# untitled.net
KiCad netlist of a schematic drawn in EAGLE
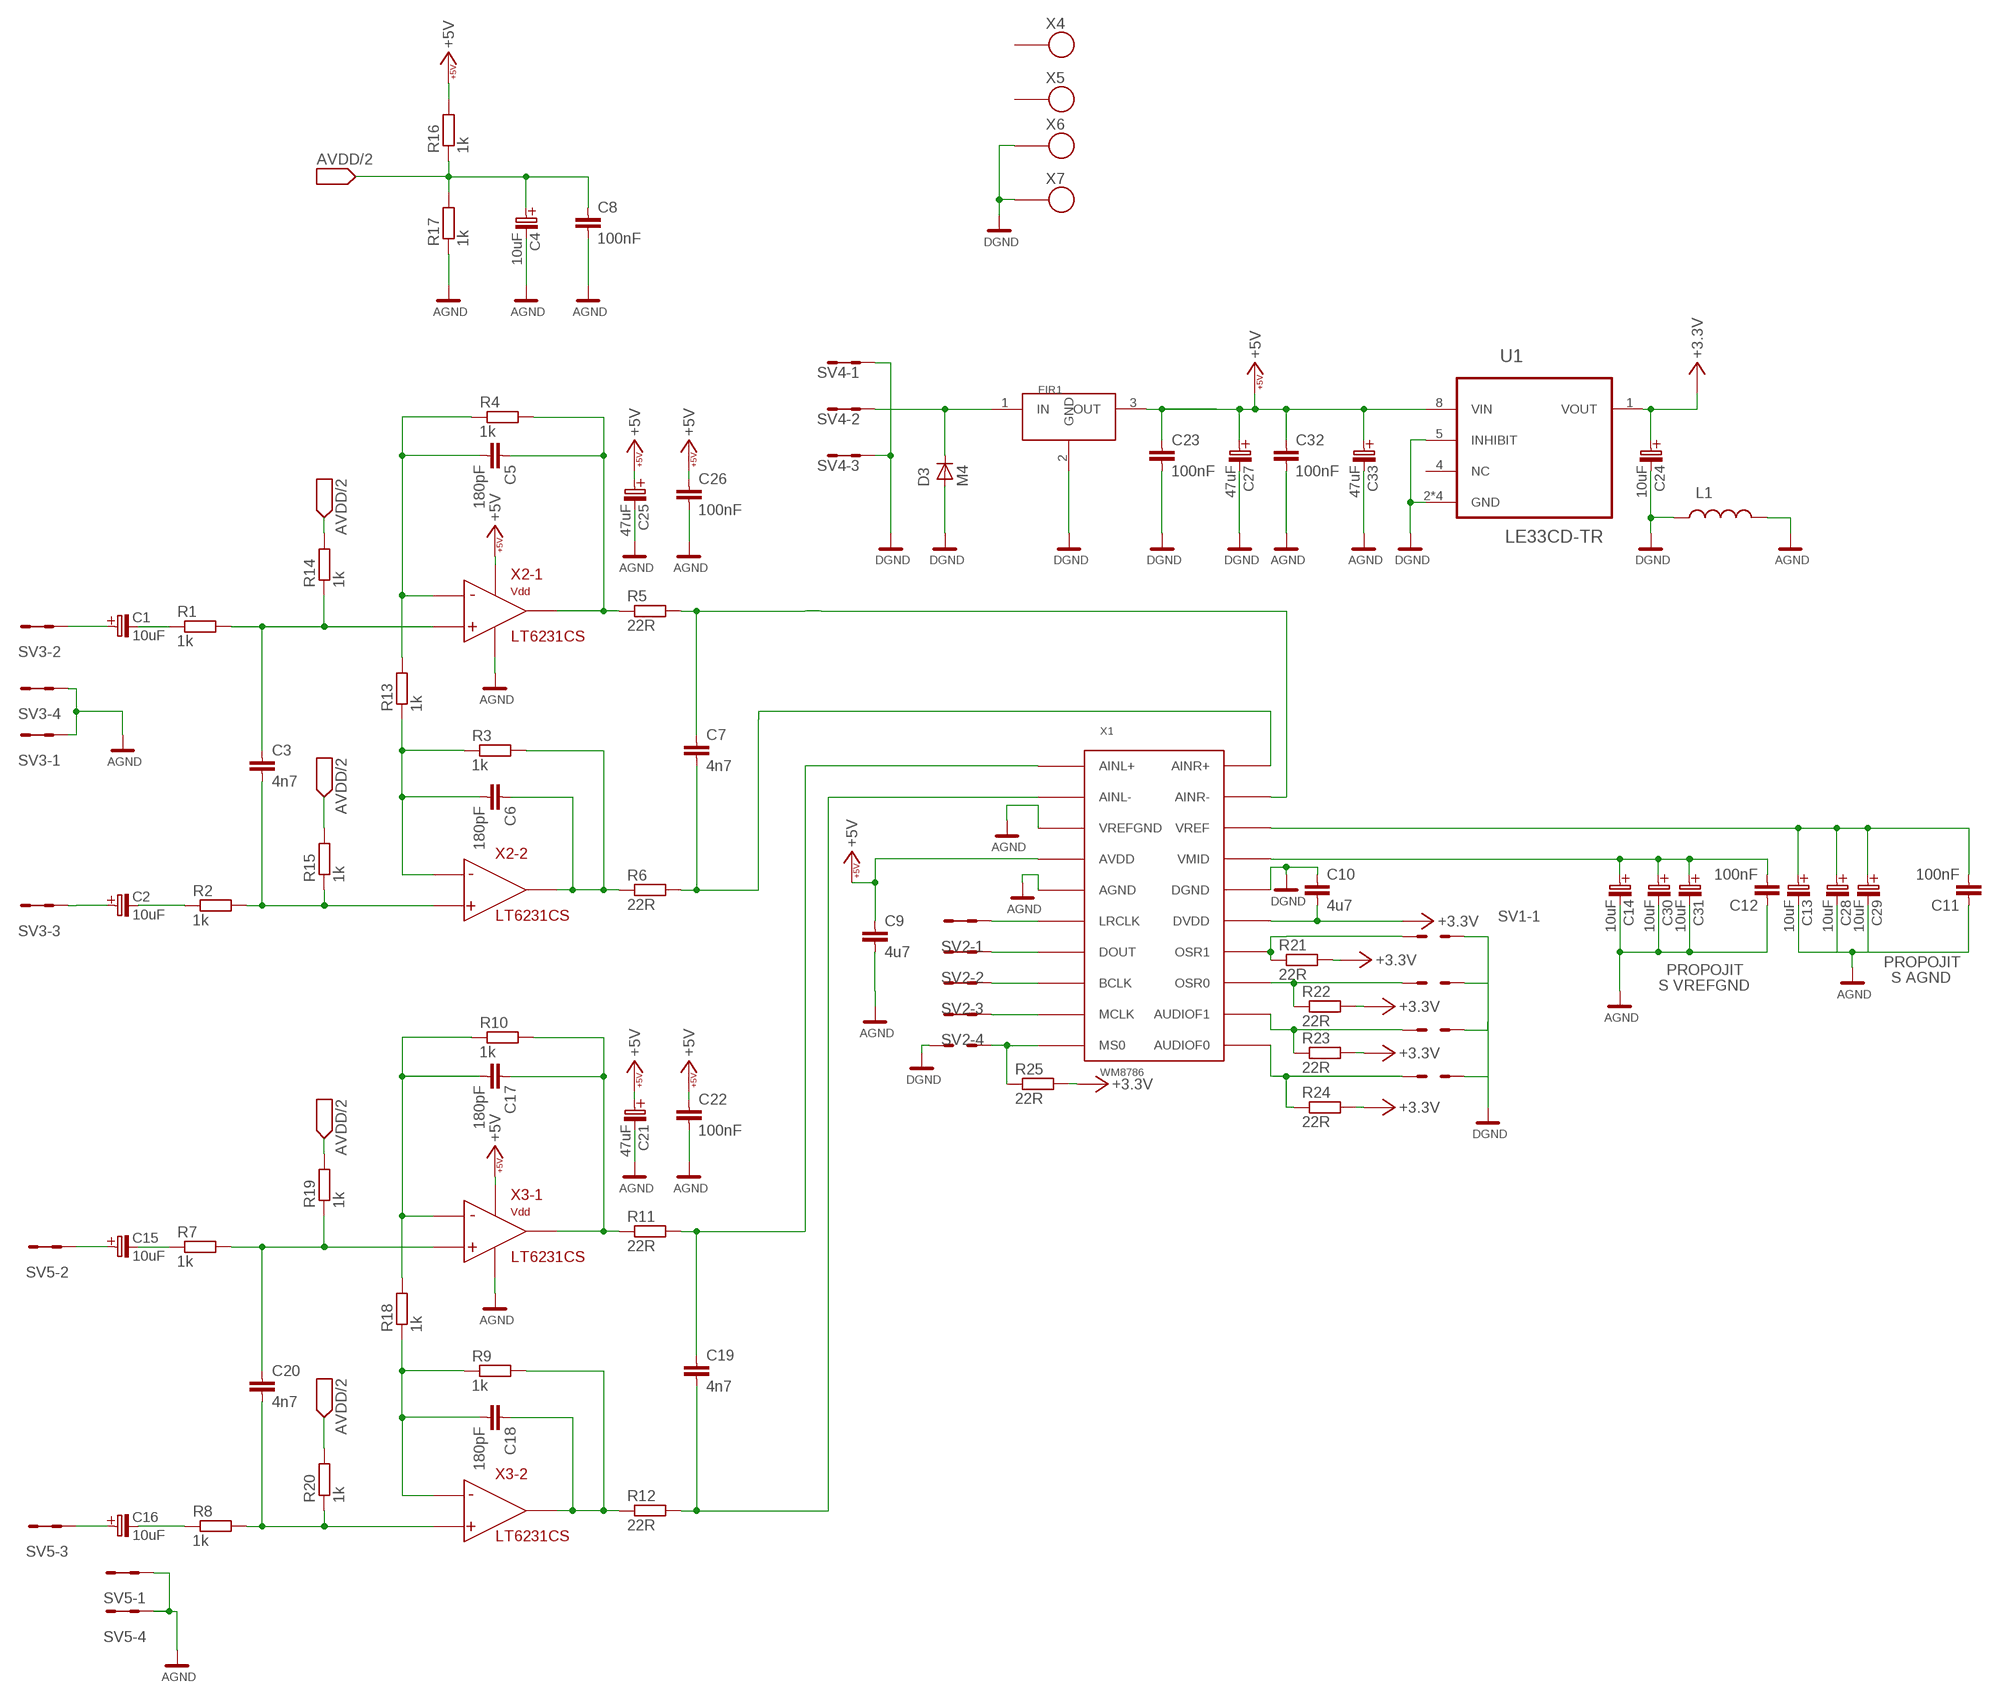
[diagram p0: schematic, sheet 1]

(export (version "E")
  (design (tool "Eeschema 10.0.6"))
  (components
    (comp (ref "C1") (value "10uF") (footprint "eagle-import:B") (libsource (lib "eagle-import") (part "B")))
    (comp (ref "C2") (value "10uF") (footprint "eagle-import:B") (libsource (lib "eagle-import") (part "B")))
    (comp (ref "C3")
      (value "4n7")
      (footprint "eagle-import:C0805")
      (libsource (lib "eagle-import") (part "C0805"))
    )
    (comp (ref "C4") (value "10uF") (footprint "eagle-import:B") (libsource (lib "eagle-import") (part "B")))
    (comp (ref "C5")
      (value "180pF")
      (footprint "eagle-import:C0805")
      (libsource (lib "eagle-import") (part "C0805"))
    )
    (comp (ref "C6")
      (value "180pF")
      (footprint "eagle-import:C0805")
      (libsource (lib "eagle-import") (part "C0805"))
    )
    (comp (ref "C7")
      (value "4n7")
      (footprint "eagle-import:C0805")
      (libsource (lib "eagle-import") (part "C0805"))
    )
    (comp (ref "C8")
      (value "100nF")
      (footprint "eagle-import:C0805")
      (libsource (lib "eagle-import") (part "C0805"))
    )
    (comp (ref "C9")
      (value "4u7")
      (footprint "eagle-import:C0805")
      (libsource (lib "eagle-import") (part "C0805"))
    )
    (comp (ref "C10")
      (value "4u7")
      (footprint "eagle-import:C0805")
      (libsource (lib "eagle-import") (part "C0805"))
    )
    (comp (ref "C11")
      (value "100nF")
      (footprint "eagle-import:C0805")
      (libsource (lib "eagle-import") (part "C0805"))
    )
    (comp (ref "C12")
      (value "100nF")
      (footprint "eagle-import:C0805")
      (libsource (lib "eagle-import") (part "C0805"))
    )
    (comp (ref "C13") (value "10uF") (footprint "eagle-import:B") (libsource (lib "eagle-import") (part "B")))
    (comp (ref "C14") (value "10uF") (footprint "eagle-import:B") (libsource (lib "eagle-import") (part "B")))
    (comp (ref "C15") (value "10uF") (footprint "eagle-import:B") (libsource (lib "eagle-import") (part "B")))
    (comp (ref "C16") (value "10uF") (footprint "eagle-import:B") (libsource (lib "eagle-import") (part "B")))
    (comp (ref "C17")
      (value "180pF")
      (footprint "eagle-import:C0805")
      (libsource (lib "eagle-import") (part "C0805"))
    )
    (comp (ref "C18")
      (value "180pF")
      (footprint "eagle-import:C0805")
      (libsource (lib "eagle-import") (part "C0805"))
    )
    (comp (ref "C19")
      (value "4n7")
      (footprint "eagle-import:C0805")
      (libsource (lib "eagle-import") (part "C0805"))
    )
    (comp (ref "C20")
      (value "4n7")
      (footprint "eagle-import:C0805")
      (libsource (lib "eagle-import") (part "C0805"))
    )
    (comp (ref "C21") (value "47uF") (footprint "eagle-import:B") (libsource (lib "eagle-import") (part "B")))
    (comp (ref "C22")
      (value "100nF")
      (footprint "eagle-import:C0805")
      (libsource (lib "eagle-import") (part "C0805"))
    )
    (comp (ref "C23")
      (value "100nF")
      (footprint "eagle-import:C0805")
      (libsource (lib "eagle-import") (part "C0805"))
    )
    (comp (ref "C24") (value "10uF") (footprint "eagle-import:B") (libsource (lib "eagle-import") (part "B")))
    (comp (ref "C25") (value "47uF") (footprint "eagle-import:B") (libsource (lib "eagle-import") (part "B")))
    (comp (ref "C26")
      (value "100nF")
      (footprint "eagle-import:C0805")
      (libsource (lib "eagle-import") (part "C0805"))
    )
    (comp (ref "C27") (value "47uF") (footprint "eagle-import:B") (libsource (lib "eagle-import") (part "B")))
    (comp (ref "C28") (value "10uF") (footprint "eagle-import:B") (libsource (lib "eagle-import") (part "B")))
    (comp (ref "C29") (value "10uF") (footprint "eagle-import:B") (libsource (lib "eagle-import") (part "B")))
    (comp (ref "C30") (value "10uF") (footprint "eagle-import:B") (libsource (lib "eagle-import") (part "B")))
    (comp (ref "C31") (value "10uF") (footprint "eagle-import:B") (libsource (lib "eagle-import") (part "B")))
    (comp (ref "C32")
      (value "100nF")
      (footprint "eagle-import:C0805")
      (libsource (lib "eagle-import") (part "C0805"))
    )
    (comp (ref "C33") (value "47uF") (footprint "eagle-import:B") (libsource (lib "eagle-import") (part "B")))
    (comp (ref "D3")
      (value "M4")
      (footprint "eagle-import:SMA")
      (libsource (lib "eagle-import") (part "D-OB.SMA"))
    )
    (comp (ref "FIR1")
      (value "FILTR0805")
      (footprint "eagle-import:F0805")
      (libsource (lib "eagle-import") (part "FILTR0805"))
    )
    (comp (ref "L1")
      (value "L0805")
      (footprint "eagle-import:L0805")
      (libsource (lib "eagle-import") (part "L0805"))
    )
    (comp (ref "R1")
      (value "1k")
      (footprint "eagle-import:0805")
      (libsource (lib "eagle-import") (part "R0805"))
    )
    (comp (ref "R2")
      (value "1k")
      (footprint "eagle-import:0805")
      (libsource (lib "eagle-import") (part "R0805"))
    )
    (comp (ref "R3")
      (value "1k")
      (footprint "eagle-import:0805")
      (libsource (lib "eagle-import") (part "R0805"))
    )
    (comp (ref "R4")
      (value "1k")
      (footprint "eagle-import:0805")
      (libsource (lib "eagle-import") (part "R0805"))
    )
    (comp (ref "R5")
      (value "22R")
      (footprint "eagle-import:0805")
      (libsource (lib "eagle-import") (part "R0805"))
    )
    (comp (ref "R6")
      (value "22R")
      (footprint "eagle-import:0805")
      (libsource (lib "eagle-import") (part "R0805"))
    )
    (comp (ref "R7")
      (value "1k")
      (footprint "eagle-import:0805")
      (libsource (lib "eagle-import") (part "R0805"))
    )
    (comp (ref "R8")
      (value "1k")
      (footprint "eagle-import:0805")
      (libsource (lib "eagle-import") (part "R0805"))
    )
    (comp (ref "R9")
      (value "1k")
      (footprint "eagle-import:0805")
      (libsource (lib "eagle-import") (part "R0805"))
    )
    (comp (ref "R10")
      (value "1k")
      (footprint "eagle-import:0805")
      (libsource (lib "eagle-import") (part "R0805"))
    )
    (comp (ref "R11")
      (value "22R")
      (footprint "eagle-import:0805")
      (libsource (lib "eagle-import") (part "R0805"))
    )
    (comp (ref "R12")
      (value "22R")
      (footprint "eagle-import:0805")
      (libsource (lib "eagle-import") (part "R0805"))
    )
    (comp (ref "R13")
      (value "1k")
      (footprint "eagle-import:0805")
      (libsource (lib "eagle-import") (part "R0805"))
    )
    (comp (ref "R14")
      (value "1k")
      (footprint "eagle-import:0805")
      (libsource (lib "eagle-import") (part "R0805"))
    )
    (comp (ref "R15")
      (value "1k")
      (footprint "eagle-import:0805")
      (libsource (lib "eagle-import") (part "R0805"))
    )
    (comp (ref "R16")
      (value "1k")
      (footprint "eagle-import:0805")
      (libsource (lib "eagle-import") (part "R0805"))
    )
    (comp (ref "R17")
      (value "1k")
      (footprint "eagle-import:0805")
      (libsource (lib "eagle-import") (part "R0805"))
    )
    (comp (ref "R18")
      (value "1k")
      (footprint "eagle-import:0805")
      (libsource (lib "eagle-import") (part "R0805"))
    )
    (comp (ref "R19")
      (value "1k")
      (footprint "eagle-import:0805")
      (libsource (lib "eagle-import") (part "R0805"))
    )
    (comp (ref "R20")
      (value "1k")
      (footprint "eagle-import:0805")
      (libsource (lib "eagle-import") (part "R0805"))
    )
    (comp (ref "R21")
      (value "22R")
      (footprint "eagle-import:0805")
      (libsource (lib "eagle-import") (part "R0805"))
    )
    (comp (ref "R22")
      (value "22R")
      (footprint "eagle-import:0805")
      (libsource (lib "eagle-import") (part "R0805"))
    )
    (comp (ref "R23")
      (value "22R")
      (footprint "eagle-import:0805")
      (libsource (lib "eagle-import") (part "R0805"))
    )
    (comp (ref "R24")
      (value "22R")
      (footprint "eagle-import:0805")
      (libsource (lib "eagle-import") (part "R0805"))
    )
    (comp (ref "R25")
      (value "22R")
      (footprint "eagle-import:0805")
      (libsource (lib "eagle-import") (part "R0805"))
    )
    (comp (ref "SV1")
      (value "MA05-3")
      (footprint "eagle-import:MA05-2")
      (libsource (lib "eagle-import") (part "MA05-3"))
    )
    (comp (ref "SV2")
      (value "MA04-2")
      (footprint "eagle-import:MA04-2")
      (libsource (lib "eagle-import") (part "MA04-2"))
    )
    (comp (ref "SV3")
      (value "MA04-2")
      (footprint "eagle-import:MA04-2")
      (libsource (lib "eagle-import") (part "MA04-2"))
    )
    (comp (ref "SV4")
      (value "MA03-2")
      (footprint "eagle-import:MA03-2")
      (libsource (lib "eagle-import") (part "MA03-2"))
    )
    (comp (ref "SV5")
      (value "MA04-2")
      (footprint "eagle-import:MA04-2")
      (libsource (lib "eagle-import") (part "MA04-2"))
    )
    (comp (ref "U1")
      (value "LE33CD-TR")
      (footprint "eagle-import:SOIC127P600X175-8N")
      (libsource (lib "eagle-import") (part "LE33CD-TR"))
    )
    (comp (ref "X1")
      (value "WM8786")
      (footprint "eagle-import:SSOP20")
      (libsource (lib "eagle-import") (part "WM8786"))
    )
    (comp (ref "X2")
      (value "LT6231CS")
      (footprint "eagle-import:SO8")
      (libsource (lib "eagle-import") (part "LT6231CS"))
    )
    (comp (ref "X3")
      (value "LT6231CS")
      (footprint "eagle-import:SO8")
      (libsource (lib "eagle-import") (part "LT6231CS"))
    )
    (comp (ref "X4")
      (value "SROUB3M")
      (footprint "eagle-import:SROUB3M")
      (libsource (lib "eagle-import") (part "SROUB3M"))
    )
    (comp (ref "X5")
      (value "SROUB3M")
      (footprint "eagle-import:SROUB3M")
      (libsource (lib "eagle-import") (part "SROUB3M"))
    )
    (comp (ref "X6")
      (value "SROUB3M")
      (footprint "eagle-import:SROUB3M")
      (libsource (lib "eagle-import") (part "SROUB3M"))
    )
    (comp (ref "X7")
      (value "SROUB3M")
      (footprint "eagle-import:SROUB3M")
      (libsource (lib "eagle-import") (part "SROUB3M"))
    )
  )
  (nets
    (net (code "1") (name "+3.3V") (class "Default")
      (node (ref "C10") (pin "2") (pinfunction "2_2") (pintype "passive"))
      (node (ref "C24") (pin "+") (pinfunction "C_EL+_+") (pintype "passive"))
      (node (ref "R21") (pin "2") (pinfunction "2_2") (pintype "passive"))
      (node (ref "R22") (pin "2") (pinfunction "2_2") (pintype "passive"))
      (node (ref "R23") (pin "2") (pinfunction "2_2") (pintype "passive"))
      (node (ref "R24") (pin "2") (pinfunction "2_2") (pintype "passive"))
      (node (ref "R25") (pin "2") (pinfunction "2_2") (pintype "passive"))
      (node (ref "U1") (pin "1") (pinfunction "VOUT_1") (pintype "output"))
      (node (ref "X1") (pin "15") (pinfunction "DVDD_15") (pintype "bidirectional"))
    )
    (net (code "2") (name "+5V") (class "Default")
      (node (ref "C21") (pin "+") (pinfunction "C_EL+_+") (pintype "passive"))
      (node (ref "C22") (pin "1") (pinfunction "1_1") (pintype "passive"))
      (node (ref "C23") (pin "1") (pinfunction "1_1") (pintype "passive"))
      (node (ref "C25") (pin "+") (pinfunction "C_EL+_+") (pintype "passive"))
      (node (ref "C26") (pin "1") (pinfunction "1_1") (pintype "passive"))
      (node (ref "C27") (pin "+") (pinfunction "C_EL+_+") (pintype "passive"))
      (node (ref "C32") (pin "1") (pinfunction "1_1") (pintype "passive"))
      (node (ref "C33") (pin "+") (pinfunction "C_EL+_+") (pintype "passive"))
      (node (ref "C9") (pin "1") (pinfunction "1_1") (pintype "passive"))
      (node (ref "FIR1") (pin "3") (pinfunction "OUT_3") (pintype "bidirectional"))
      (node (ref "R16") (pin "2") (pinfunction "2_2") (pintype "passive"))
      (node (ref "U1") (pin "8") (pinfunction "VIN_8") (pintype "power_in"))
      (node (ref "X1") (pin "4") (pinfunction "AVDD_4") (pintype "bidirectional"))
      (node (ref "X2") (pin "8") (pinfunction "VDD_8") (pintype "bidirectional"))
      (node (ref "X3") (pin "8") (pinfunction "VDD_8") (pintype "bidirectional"))
    )
    (net (code "3") (name "/AVDD{slash}2") (class "Default")
      (node (ref "C4") (pin "+") (pinfunction "C_EL+_+") (pintype "passive"))
      (node (ref "C8") (pin "1") (pinfunction "1_1") (pintype "passive"))
      (node (ref "R14") (pin "2") (pinfunction "2_2") (pintype "passive"))
      (node (ref "R15") (pin "2") (pinfunction "2_2") (pintype "passive"))
      (node (ref "R16") (pin "1") (pinfunction "1_1") (pintype "passive"))
      (node (ref "R17") (pin "2") (pinfunction "2_2") (pintype "passive"))
      (node (ref "R19") (pin "2") (pinfunction "2_2") (pintype "passive"))
      (node (ref "R20") (pin "2") (pinfunction "2_2") (pintype "passive"))
    )
    (net (code "4") (name "AGND") (class "Default")
      (node (ref "C11") (pin "1") (pinfunction "1_1") (pintype "passive"))
      (node (ref "C12") (pin "1") (pinfunction "1_1") (pintype "passive"))
      (node (ref "C13") (pin "-") (pinfunction "C_EL-_-") (pintype "passive"))
      (node (ref "C14") (pin "-") (pinfunction "C_EL-_-") (pintype "passive"))
      (node (ref "C21") (pin "-") (pinfunction "C_EL-_-") (pintype "passive"))
      (node (ref "C22") (pin "2") (pinfunction "2_2") (pintype "passive"))
      (node (ref "C25") (pin "-") (pinfunction "C_EL-_-") (pintype "passive"))
      (node (ref "C26") (pin "2") (pinfunction "2_2") (pintype "passive"))
      (node (ref "C28") (pin "-") (pinfunction "C_EL-_-") (pintype "passive"))
      (node (ref "C29") (pin "-") (pinfunction "C_EL-_-") (pintype "passive"))
      (node (ref "C30") (pin "-") (pinfunction "C_EL-_-") (pintype "passive"))
      (node (ref "C31") (pin "-") (pinfunction "C_EL-_-") (pintype "passive"))
      (node (ref "C32") (pin "2") (pinfunction "2_2") (pintype "passive"))
      (node (ref "C33") (pin "-") (pinfunction "C_EL-_-") (pintype "passive"))
      (node (ref "C4") (pin "-") (pinfunction "C_EL-_-") (pintype "passive"))
      (node (ref "C8") (pin "2") (pinfunction "2_2") (pintype "passive"))
      (node (ref "C9") (pin "2") (pinfunction "2_2") (pintype "passive"))
      (node (ref "L1") (pin "2") (pinfunction "2_2") (pintype "passive"))
      (node (ref "R17") (pin "1") (pinfunction "1_1") (pintype "passive"))
      (node (ref "SV3") (pin "1") (pinfunction "K_1") (pintype "passive"))
      (node (ref "SV3") (pin "2") (pinfunction "K_2") (pintype "passive"))
      (node (ref "SV3") (pin "7") (pinfunction "K_7") (pintype "passive"))
      (node (ref "SV3") (pin "8") (pinfunction "K_8") (pintype "passive"))
      (node (ref "SV5") (pin "1") (pinfunction "K_1") (pintype "passive"))
      (node (ref "SV5") (pin "2") (pinfunction "K_2") (pintype "passive"))
      (node (ref "SV5") (pin "7") (pinfunction "K_7") (pintype "passive"))
      (node (ref "SV5") (pin "8") (pinfunction "K_8") (pintype "passive"))
      (node (ref "X1") (pin "3") (pinfunction "VREFGND_3") (pintype "bidirectional"))
      (node (ref "X1") (pin "5") (pinfunction "AGND_5") (pintype "bidirectional"))
      (node (ref "X2") (pin "4") (pinfunction "GND_4") (pintype "bidirectional"))
      (node (ref "X3") (pin "4") (pinfunction "GND_4") (pintype "bidirectional"))
    )
    (net (code "5") (name "DGND") (class "Default")
      (node (ref "C10") (pin "1") (pinfunction "1_1") (pintype "passive"))
      (node (ref "C23") (pin "2") (pinfunction "2_2") (pintype "passive"))
      (node (ref "C24") (pin "-") (pinfunction "C_EL-_-") (pintype "passive"))
      (node (ref "C27") (pin "-") (pinfunction "C_EL-_-") (pintype "passive"))
      (node (ref "D3") (pin "A") (pinfunction "A_A") (pintype "passive"))
      (node (ref "FIR1") (pin "2") (pinfunction "GND_2") (pintype "passive"))
      (node (ref "L1") (pin "1") (pinfunction "1_1") (pintype "passive"))
      (node (ref "SV1") (pin "1") (pinfunction "P$1_1") (pintype "passive"))
      (node (ref "SV1") (pin "3") (pinfunction "P$1_3") (pintype "passive"))
      (node (ref "SV1") (pin "5") (pinfunction "P$1_5") (pintype "passive"))
      (node (ref "SV1") (pin "7") (pinfunction "P$1_7") (pintype "passive"))
      (node (ref "SV1") (pin "9") (pinfunction "P$1_9") (pintype "passive"))
      (node (ref "SV4") (pin "1") (pinfunction "K_1") (pintype "passive"))
      (node (ref "SV4") (pin "2") (pinfunction "K_2") (pintype "passive"))
      (node (ref "SV4") (pin "5") (pinfunction "K_5") (pintype "passive"))
      (node (ref "SV4") (pin "6") (pinfunction "K_6") (pintype "passive"))
      (node (ref "U1") (pin "2") (pinfunction "GND_2") (pintype "passive"))
      (node (ref "U1") (pin "3") (pinfunction "GND_3") (pintype "passive"))
      (node (ref "U1") (pin "5") (pinfunction "INHIBIT_5") (pintype "passive"))
      (node (ref "U1") (pin "6") (pinfunction "GND_6") (pintype "passive"))
      (node (ref "U1") (pin "7") (pinfunction "GND_7") (pintype "passive"))
      (node (ref "X1") (pin "16") (pinfunction "DGND_16") (pintype "bidirectional"))
      (node (ref "X6") (pin "P$1") (pinfunction "P$1_P$1") (pintype "bidirectional"))
      (node (ref "X7") (pin "P$1") (pinfunction "P$1_P$1") (pintype "bidirectional"))
    )
    (net (code "6") (name "Net-(C1-C_EL+)") (class "Default")
      (node (ref "C1") (pin "+") (pinfunction "C_EL+_+") (pintype "passive"))
      (node (ref "SV3") (pin "3") (pinfunction "K_3") (pintype "passive"))
      (node (ref "SV3") (pin "4") (pinfunction "K_4") (pintype "passive"))
    )
    (net (code "7") (name "Net-(C1-C_EL-)") (class "Default")
      (node (ref "C1") (pin "-") (pinfunction "C_EL-_-") (pintype "passive"))
      (node (ref "R1") (pin "1") (pinfunction "1_1") (pintype "passive"))
    )
    (net (code "8") (name "Net-(C2-C_EL+)") (class "Default")
      (node (ref "C2") (pin "+") (pinfunction "C_EL+_+") (pintype "passive"))
      (node (ref "SV3") (pin "5") (pinfunction "K_5") (pintype "passive"))
      (node (ref "SV3") (pin "6") (pinfunction "K_6") (pintype "passive"))
    )
    (net (code "9") (name "Net-(C2-C_EL-)") (class "Default")
      (node (ref "C2") (pin "-") (pinfunction "C_EL-_-") (pintype "passive"))
      (node (ref "R2") (pin "1") (pinfunction "1_1") (pintype "passive"))
    )
    (net (code "10") (name "Net-(C13-C_EL+)") (class "Default")
      (node (ref "C11") (pin "2") (pinfunction "2_2") (pintype "passive"))
      (node (ref "C13") (pin "+") (pinfunction "C_EL+_+") (pintype "passive"))
      (node (ref "C28") (pin "+") (pinfunction "C_EL+_+") (pintype "passive"))
      (node (ref "C29") (pin "+") (pinfunction "C_EL+_+") (pintype "passive"))
      (node (ref "X1") (pin "18") (pinfunction "VREF_18") (pintype "bidirectional"))
    )
    (net (code "11") (name "Net-(C14-C_EL+)") (class "Default")
      (node (ref "C12") (pin "2") (pinfunction "2_2") (pintype "passive"))
      (node (ref "C14") (pin "+") (pinfunction "C_EL+_+") (pintype "passive"))
      (node (ref "C30") (pin "+") (pinfunction "C_EL+_+") (pintype "passive"))
      (node (ref "C31") (pin "+") (pinfunction "C_EL+_+") (pintype "passive"))
      (node (ref "X1") (pin "17") (pinfunction "VMID_17") (pintype "bidirectional"))
    )
    (net (code "12") (name "Net-(C15-C_EL+)") (class "Default")
      (node (ref "C15") (pin "+") (pinfunction "C_EL+_+") (pintype "passive"))
      (node (ref "SV5") (pin "3") (pinfunction "K_3") (pintype "passive"))
      (node (ref "SV5") (pin "4") (pinfunction "K_4") (pintype "passive"))
    )
    (net (code "13") (name "Net-(C15-C_EL-)") (class "Default")
      (node (ref "C15") (pin "-") (pinfunction "C_EL-_-") (pintype "passive"))
      (node (ref "R7") (pin "1") (pinfunction "1_1") (pintype "passive"))
    )
    (net (code "14") (name "Net-(C16-C_EL+)") (class "Default")
      (node (ref "C16") (pin "+") (pinfunction "C_EL+_+") (pintype "passive"))
      (node (ref "SV5") (pin "5") (pinfunction "K_5") (pintype "passive"))
      (node (ref "SV5") (pin "6") (pinfunction "K_6") (pintype "passive"))
    )
    (net (code "15") (name "Net-(C16-C_EL-)") (class "Default")
      (node (ref "C16") (pin "-") (pinfunction "C_EL-_-") (pintype "passive"))
      (node (ref "R8") (pin "1") (pinfunction "1_1") (pintype "passive"))
    )
    (net (code "16") (name "Net-(D3-C)") (class "Default")
      (node (ref "D3") (pin "K") (pinfunction "C_K") (pintype "passive"))
      (node (ref "FIR1") (pin "1") (pinfunction "IN_1") (pintype "bidirectional"))
      (node (ref "SV4") (pin "3") (pinfunction "K_3") (pintype "passive"))
      (node (ref "SV4") (pin "4") (pinfunction "K_4") (pintype "passive"))
    )
    (net (code "17") (name "Net-(SV1B-P$1)") (class "Default")
      (node (ref "R25") (pin "1") (pinfunction "1_1") (pintype "passive"))
      (node (ref "SV1") (pin "10") (pinfunction "P$1_10") (pintype "passive"))
      (node (ref "X1") (pin "10") (pinfunction "MS0_10") (pintype "bidirectional"))
    )
    (net (code "18") (name "Net-(SV1C-P$1)") (class "Default")
      (node (ref "R21") (pin "1") (pinfunction "1_1") (pintype "passive"))
      (node (ref "SV1") (pin "2") (pinfunction "P$1_2") (pintype "passive"))
      (node (ref "X1") (pin "14") (pinfunction "OSR1_14") (pintype "bidirectional"))
    )
    (net (code "19") (name "Net-(SV1E-P$1)") (class "Default")
      (node (ref "R22") (pin "1") (pinfunction "1_1") (pintype "passive"))
      (node (ref "SV1") (pin "4") (pinfunction "P$1_4") (pintype "passive"))
      (node (ref "X1") (pin "13") (pinfunction "OSR0_13") (pintype "bidirectional"))
    )
    (net (code "20") (name "Net-(SV1G-P$1)") (class "Default")
      (node (ref "R23") (pin "1") (pinfunction "1_1") (pintype "passive"))
      (node (ref "SV1") (pin "6") (pinfunction "P$1_6") (pintype "passive"))
      (node (ref "X1") (pin "12") (pinfunction "AUDIOF1_12") (pintype "bidirectional"))
    )
    (net (code "21") (name "Net-(SV1I-P$1)") (class "Default")
      (node (ref "R24") (pin "1") (pinfunction "1_1") (pintype "passive"))
      (node (ref "SV1") (pin "8") (pinfunction "P$1_8") (pintype "passive"))
      (node (ref "X1") (pin "11") (pinfunction "AUDIOF0_11") (pintype "bidirectional"))
    )
    (net (code "22") (name "Net-(X1-AINL+)") (class "Default")
      (node (ref "C19") (pin "1") (pinfunction "1_1") (pintype "passive"))
      (node (ref "R11") (pin "2") (pinfunction "2_2") (pintype "passive"))
      (node (ref "X1") (pin "1") (pinfunction "AINL+_1") (pintype "bidirectional"))
    )
    (net (code "23") (name "Net-(X1-AINL-)") (class "Default")
      (node (ref "C19") (pin "2") (pinfunction "2_2") (pintype "passive"))
      (node (ref "R12") (pin "2") (pinfunction "2_2") (pintype "passive"))
      (node (ref "X1") (pin "2") (pinfunction "AINL-_2") (pintype "bidirectional"))
    )
    (net (code "24") (name "Net-(X1-AINR+)") (class "Default")
      (node (ref "C7") (pin "2") (pinfunction "2_2") (pintype "passive"))
      (node (ref "R6") (pin "2") (pinfunction "2_2") (pintype "passive"))
      (node (ref "X1") (pin "20") (pinfunction "AINR+_20") (pintype "bidirectional"))
    )
    (net (code "25") (name "Net-(X1-AINR-)") (class "Default")
      (node (ref "C7") (pin "1") (pinfunction "1_1") (pintype "passive"))
      (node (ref "R5") (pin "2") (pinfunction "2_2") (pintype "passive"))
      (node (ref "X1") (pin "19") (pinfunction "AINR-_19") (pintype "bidirectional"))
    )
    (net (code "26") (name "Net-(X1-BCLK)") (class "Default")
      (node (ref "SV2") (pin "5") (pinfunction "K_5") (pintype "passive"))
      (node (ref "SV2") (pin "6") (pinfunction "K_6") (pintype "passive"))
      (node (ref "X1") (pin "8") (pinfunction "BCLK_8") (pintype "bidirectional"))
    )
    (net (code "27") (name "Net-(X1-DOUT)") (class "Default")
      (node (ref "SV2") (pin "3") (pinfunction "K_3") (pintype "passive"))
      (node (ref "SV2") (pin "4") (pinfunction "K_4") (pintype "passive"))
      (node (ref "X1") (pin "7") (pinfunction "DOUT_7") (pintype "bidirectional"))
    )
    (net (code "28") (name "Net-(X1-LRCLK)") (class "Default")
      (node (ref "SV2") (pin "1") (pinfunction "K_1") (pintype "passive"))
      (node (ref "SV2") (pin "2") (pinfunction "K_2") (pintype "passive"))
      (node (ref "X1") (pin "6") (pinfunction "LRCLK_6") (pintype "bidirectional"))
    )
    (net (code "29") (name "Net-(X1-MCLK)") (class "Default")
      (node (ref "SV2") (pin "7") (pinfunction "K_7") (pintype "passive"))
      (node (ref "SV2") (pin "8") (pinfunction "K_8") (pintype "passive"))
      (node (ref "X1") (pin "9") (pinfunction "MCLK_9") (pintype "bidirectional"))
    )
    (net (code "30") (name "Net-(X2A-+)") (class "Default")
      (node (ref "C3") (pin "1") (pinfunction "1_1") (pintype "passive"))
      (node (ref "R1") (pin "2") (pinfunction "2_2") (pintype "passive"))
      (node (ref "R14") (pin "1") (pinfunction "1_1") (pintype "passive"))
      (node (ref "X2") (pin "3") (pinfunction "+_3") (pintype "bidirectional"))
    )
    (net (code "31") (name "Net-(X2A--)") (class "Default")
      (node (ref "C5") (pin "2") (pinfunction "2_2") (pintype "passive"))
      (node (ref "R13") (pin "2") (pinfunction "2_2") (pintype "passive"))
      (node (ref "R4") (pin "1") (pinfunction "1_1") (pintype "passive"))
      (node (ref "X2") (pin "2") (pinfunction "-_2") (pintype "bidirectional"))
    )
    (net (code "32") (name "Net-(X2A-VOUT)") (class "Default")
      (node (ref "C5") (pin "1") (pinfunction "1_1") (pintype "passive"))
      (node (ref "R4") (pin "2") (pinfunction "2_2") (pintype "passive"))
      (node (ref "R5") (pin "1") (pinfunction "1_1") (pintype "passive"))
      (node (ref "X2") (pin "1") (pinfunction "VOUT_1") (pintype "bidirectional"))
    )
    (net (code "33") (name "Net-(X2B-+)") (class "Default")
      (node (ref "C3") (pin "2") (pinfunction "2_2") (pintype "passive"))
      (node (ref "R15") (pin "1") (pinfunction "1_1") (pintype "passive"))
      (node (ref "R2") (pin "2") (pinfunction "2_2") (pintype "passive"))
      (node (ref "X2") (pin "5") (pinfunction "+_5") (pintype "bidirectional"))
    )
    (net (code "34") (name "Net-(X2B--)") (class "Default")
      (node (ref "C6") (pin "2") (pinfunction "2_2") (pintype "passive"))
      (node (ref "R13") (pin "1") (pinfunction "1_1") (pintype "passive"))
      (node (ref "R3") (pin "1") (pinfunction "1_1") (pintype "passive"))
      (node (ref "X2") (pin "6") (pinfunction "-_6") (pintype "bidirectional"))
    )
    (net (code "35") (name "Net-(X2B-VOUT)") (class "Default")
      (node (ref "C6") (pin "1") (pinfunction "1_1") (pintype "passive"))
      (node (ref "R3") (pin "2") (pinfunction "2_2") (pintype "passive"))
      (node (ref "R6") (pin "1") (pinfunction "1_1") (pintype "passive"))
      (node (ref "X2") (pin "7") (pinfunction "VOUT_7") (pintype "bidirectional"))
    )
    (net (code "36") (name "Net-(X3A-+)") (class "Default")
      (node (ref "C20") (pin "1") (pinfunction "1_1") (pintype "passive"))
      (node (ref "R19") (pin "1") (pinfunction "1_1") (pintype "passive"))
      (node (ref "R7") (pin "2") (pinfunction "2_2") (pintype "passive"))
      (node (ref "X3") (pin "3") (pinfunction "+_3") (pintype "bidirectional"))
    )
    (net (code "37") (name "Net-(X3A--)") (class "Default")
      (node (ref "C17") (pin "2") (pinfunction "2_2") (pintype "passive"))
      (node (ref "R10") (pin "1") (pinfunction "1_1") (pintype "passive"))
      (node (ref "R18") (pin "2") (pinfunction "2_2") (pintype "passive"))
      (node (ref "X3") (pin "2") (pinfunction "-_2") (pintype "bidirectional"))
    )
    (net (code "38") (name "Net-(X3A-VOUT)") (class "Default")
      (node (ref "C17") (pin "1") (pinfunction "1_1") (pintype "passive"))
      (node (ref "R10") (pin "2") (pinfunction "2_2") (pintype "passive"))
      (node (ref "R11") (pin "1") (pinfunction "1_1") (pintype "passive"))
      (node (ref "X3") (pin "1") (pinfunction "VOUT_1") (pintype "bidirectional"))
    )
    (net (code "39") (name "Net-(X3B-+)") (class "Default")
      (node (ref "C20") (pin "2") (pinfunction "2_2") (pintype "passive"))
      (node (ref "R20") (pin "1") (pinfunction "1_1") (pintype "passive"))
      (node (ref "R8") (pin "2") (pinfunction "2_2") (pintype "passive"))
      (node (ref "X3") (pin "5") (pinfunction "+_5") (pintype "bidirectional"))
    )
    (net (code "40") (name "Net-(X3B--)") (class "Default")
      (node (ref "C18") (pin "2") (pinfunction "2_2") (pintype "passive"))
      (node (ref "R18") (pin "1") (pinfunction "1_1") (pintype "passive"))
      (node (ref "R9") (pin "1") (pinfunction "1_1") (pintype "passive"))
      (node (ref "X3") (pin "6") (pinfunction "-_6") (pintype "bidirectional"))
    )
    (net (code "41") (name "Net-(X3B-VOUT)") (class "Default")
      (node (ref "C18") (pin "1") (pinfunction "1_1") (pintype "passive"))
      (node (ref "R12") (pin "1") (pinfunction "1_1") (pintype "passive"))
      (node (ref "R9") (pin "2") (pinfunction "2_2") (pintype "passive"))
      (node (ref "X3") (pin "7") (pinfunction "VOUT_7") (pintype "bidirectional"))
    )
    (net (code "42") (name "unconnected-(U1-NC-Pad4)") (class "Default")
      (node (ref "U1") (pin "4") (pinfunction "NC_4") (pintype "no_connect"))
    )
    (net (code "43") (name "unconnected-(X4-PadP$1)") (class "Default")
      (node (ref "X4") (pin "P$1") (pinfunction "P$1_P$1") (pintype "bidirectional"))
    )
    (net (code "44") (name "unconnected-(X5-PadP$1)") (class "Default")
      (node (ref "X5") (pin "P$1") (pinfunction "P$1_P$1") (pintype "bidirectional"))
    )
  )
)
